# SensorsOnly_v7.net
KiCad netlist of a schematic drawn in EAGLE
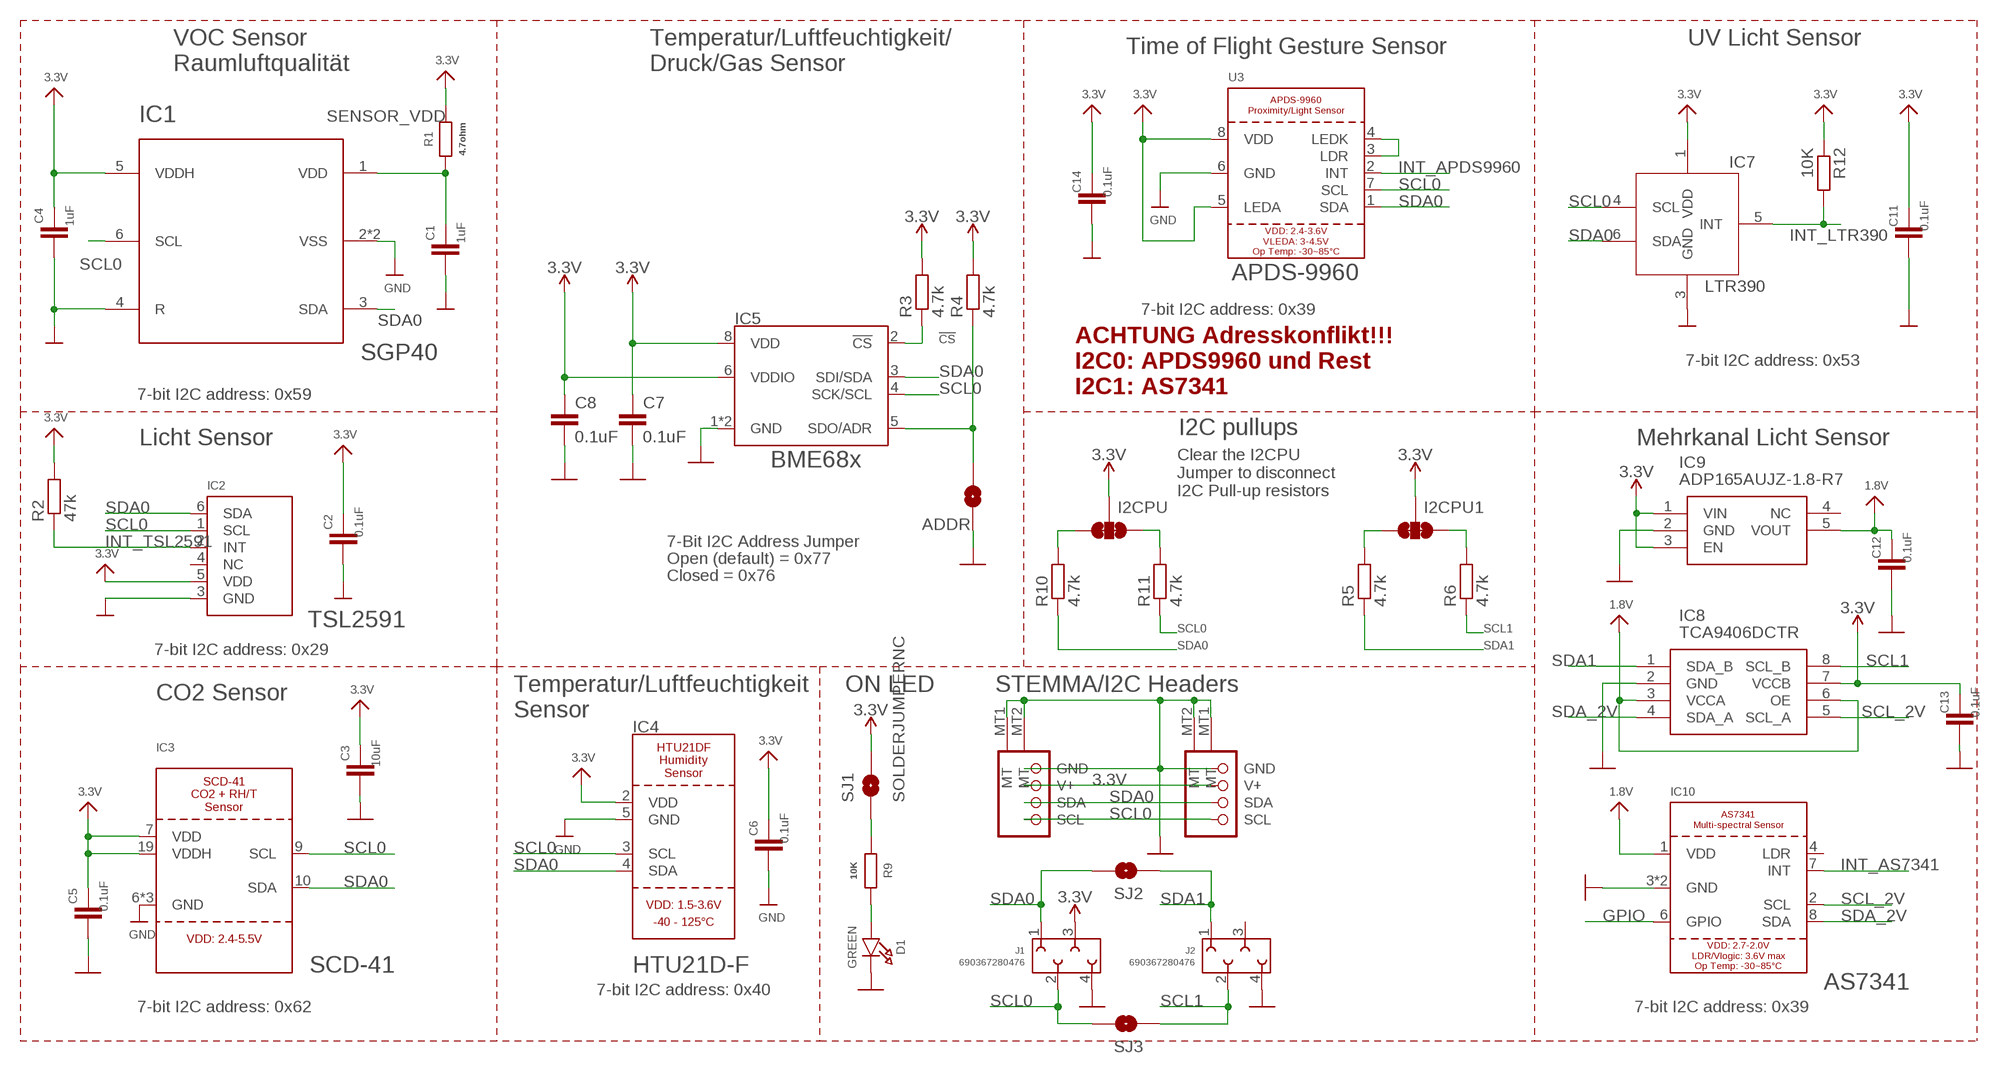
[diagram p0: schematic, sheet 1]

(export (version "E")
  (design (tool "Eeschema 10.0.6"))
  (components
    (comp (ref "ADDR")
      (value "JUMPER-SMT_2_NO_SILK")
      (footprint "eagle-import:SMT-JUMPER_2_NO_SILK")
      (libsource (lib "eagle-import") (part "JUMPER-SMT_2_NO_SILK"))
    )
    (comp (ref "C1")
      (value "1uF")
      (footprint "eagle-import:C0805")
      (libsource (lib "eagle-import") (part "C-EUC0805"))
    )
    (comp (ref "C2")
      (value "0.1uF")
      (footprint "eagle-import:C0603")
      (libsource (lib "eagle-import") (part "C-EUC0603"))
    )
    (comp (ref "C3")
      (value "10uF")
      (footprint "eagle-import:C0805")
      (libsource (lib "eagle-import") (part "C-EUC0805"))
    )
    (comp (ref "C4")
      (value "1uF")
      (footprint "eagle-import:C0805")
      (libsource (lib "eagle-import") (part "C-EUC0805"))
    )
    (comp (ref "C5")
      (value "0.1uF")
      (footprint "eagle-import:C0603")
      (libsource (lib "eagle-import") (part "C-EUC0603"))
    )
    (comp (ref "C6")
      (value "0.1uF")
      (footprint "eagle-import:C0603")
      (libsource (lib "eagle-import") (part "C-EUC0603"))
    )
    (comp (ref "C7")
      (value "0.1uF")
      (footprint "eagle-import:C0603")
      (libsource (lib "eagle-import") (part "C-EUC0603"))
    )
    (comp (ref "C8")
      (value "0.1uF")
      (footprint "eagle-import:C0603")
      (libsource (lib "eagle-import") (part "C-EUC0603"))
    )
    (comp (ref "C11")
      (value "0.1uF")
      (footprint "eagle-import:C0603")
      (libsource (lib "eagle-import") (part "C-EUC0603"))
    )
    (comp (ref "C12")
      (value "0.1uF")
      (footprint "eagle-import:C0603")
      (libsource (lib "eagle-import") (part "C-EUC0603"))
    )
    (comp (ref "C13")
      (value "0.1uF")
      (footprint "eagle-import:C0603")
      (libsource (lib "eagle-import") (part "C-EUC0603"))
    )
    (comp (ref "C14")
      (value "0.1uF")
      (footprint "eagle-import:C0603")
      (libsource (lib "eagle-import") (part "C-EUC0603"))
    )
    (comp (ref "D1")
      (value "GREEN")
      (footprint "eagle-import:CHIPLED_0603_NOOUTLINE")
      (libsource (lib "eagle-import") (part "LED0603_NOOUTLINE"))
    )
    (comp (ref "I2CPU")
      (value "I2C PU")
      (footprint "eagle-import:SMT-JUMPER_3_2-NC_TRACE_SILK")
      (libsource (lib "eagle-import") (part "JUMPER-SMT_3_2-NC_TRACE_SILK"))
    )
    (comp (ref "I2CPU1")
      (value "I2C PU")
      (footprint "eagle-import:SMT-JUMPER_3_2-NC_TRACE_SILK")
      (libsource (lib "eagle-import") (part "JUMPER-SMT_3_2-NC_TRACE_SILK"))
    )
    (comp (ref "IC1")
      (value "SGP40")
      (footprint "eagle-import:SGP30")
      (libsource (lib "eagle-import") (part "SGP30"))
    )
    (comp (ref "IC2")
      (value "TSL2591")
      (footprint "eagle-import:DFN6_TAOS")
      (libsource (lib "eagle-import") (part "LIGHT_TSL2591"))
    )
    (comp (ref "IC3")
      (value "SCD-41")
      (footprint "eagle-import:SCD41")
      (libsource (lib "eagle-import") (part "SCD-41"))
    )
    (comp (ref "IC4")
      (value "HTU21D-F")
      (footprint "eagle-import:HTU21DF")
      (libsource (lib "eagle-import") (part "HTU21DF"))
    )
    (comp (ref "IC5")
      (value "BME680 Air Quality Sensor")
      (footprint "eagle-import:LGA3.0X3.0")
      (libsource (lib "eagle-import") (part "BME680-LGA"))
    )
    (comp (ref "IC7")
      (value "LTR390")
      (footprint "eagle-import:LTR390")
      (libsource (lib "eagle-import") (part "LTR390"))
    )
    (comp (ref "IC8")
      (value "TCA9406DCTR")
      (footprint "eagle-import:SOP65P400X130-8N")
      (fields (field (name "MOUSER_PART_NUMBER") "595-TCA9406DCTR"))
      (libsource (lib "eagle-import") (part "TCA9406DCTR"))
    )
    (comp (ref "IC9")
      (value "ADP165AUJZ-1.8-R7")
      (footprint "eagle-import:SOT95P280X100-5N")
      (fields
        (field (name "MANUFACTURER_PART_NUMBER") "ADP165AUJZ-3.3-R7")
        (field (name "MOUSER_PART_NUMBER") "584-ADP165AUJZ3.3R7")
      )
      (libsource (lib "eagle-import") (part "ADP165AUJZ-3.3-R7"))
    )
    (comp (ref "IC10")
      (value "AS7341")
      (footprint "eagle-import:AS7341")
      (libsource (lib "eagle-import") (part "AS7341"))
    )
    (comp (ref "J1")
      (value "690367280476")
      (footprint "eagle-import:690367280476")
      (libsource (lib "eagle-import") (part "690367280476"))
    )
    (comp (ref "J2")
      (value "690367280476")
      (footprint "eagle-import:690367280476")
      (libsource (lib "eagle-import") (part "690367280476"))
    )
    (comp (ref "QWIIC1")
      (value "STEMMA_I2C_QT")
      (footprint "eagle-import:JST_SH4")
      (libsource (lib "eagle-import") (part "STEMMA_I2C_QT"))
    )
    (comp (ref "QWIIC2")
      (value "STEMMA_I2C_QT")
      (footprint "eagle-import:JST_SH4")
      (libsource (lib "eagle-import") (part "STEMMA_I2C_QT"))
    )
    (comp (ref "R1")
      (value "4.7ohm")
      (footprint "eagle-import:R0603")
      (libsource (lib "eagle-import") (part "R-EU_R0603"))
    )
    (comp (ref "R2")
      (value "47k")
      (footprint "eagle-import:R0603")
      (libsource (lib "eagle-import") (part "R-EU_R0603"))
    )
    (comp (ref "R3")
      (value "4.7k")
      (footprint "eagle-import:R0603")
      (libsource (lib "eagle-import") (part "R-EU_R0603"))
    )
    (comp (ref "R4")
      (value "4.7k")
      (footprint "eagle-import:R0603")
      (libsource (lib "eagle-import") (part "R-EU_R0603"))
    )
    (comp (ref "R5")
      (value "4.7k")
      (footprint "eagle-import:R0603")
      (libsource (lib "eagle-import") (part "R-EU_R0603"))
    )
    (comp (ref "R6")
      (value "4.7k")
      (footprint "eagle-import:R0603")
      (libsource (lib "eagle-import") (part "R-EU_R0603"))
    )
    (comp (ref "R9")
      (value "10K")
      (footprint "eagle-import:R0603")
      (libsource (lib "eagle-import") (part "R-EU_R0603"))
    )
    (comp (ref "R10")
      (value "4.7k")
      (footprint "eagle-import:R0603")
      (libsource (lib "eagle-import") (part "R-EU_R0603"))
    )
    (comp (ref "R11")
      (value "4.7k")
      (footprint "eagle-import:R0603")
      (libsource (lib "eagle-import") (part "R-EU_R0603"))
    )
    (comp (ref "R12")
      (value "10K")
      (footprint "eagle-import:R0603")
      (libsource (lib "eagle-import") (part "R-EU_R0603"))
    )
    (comp (ref "SJ1")
      (value "SOLDERJUMPERNC")
      (footprint "eagle-import:SJ_2S")
      (libsource (lib "eagle-import") (part "SOLDERJUMPERNC"))
    )
    (comp (ref "SJ2")
      (value "SOLDERJUMPERNC")
      (footprint "eagle-import:SJ_2S")
      (libsource (lib "eagle-import") (part "SOLDERJUMPERNC"))
    )
    (comp (ref "SJ3")
      (value "SOLDERJUMPERNC")
      (footprint "eagle-import:SJ_2S")
      (libsource (lib "eagle-import") (part "SOLDERJUMPERNC"))
    )
    (comp (ref "U3")
      (value "APDS-9960")
      (footprint "eagle-import:APDS-9960")
      (libsource (lib "eagle-import") (part "APDS-9960"))
    )
  )
  (nets
    (net (code "1") (name "/GPIO") (class "Default")
      (node (ref "IC10") (pin "6") (pinfunction "GPIO_6") (pintype "power_in"))
    )
    (net (code "2") (name "/INT_APDS9960") (class "Default")
      (node (ref "U3") (pin "2") (pinfunction "INT_2") (pintype "output"))
    )
    (net (code "3") (name "/INT_AS7341") (class "Default")
      (node (ref "IC10") (pin "7") (pinfunction "INT_7") (pintype "output"))
    )
    (net (code "4") (name "/INT_LTR390") (class "Default")
      (node (ref "IC7") (pin "5") (pinfunction "INT_5") (pintype "bidirectional"))
      (node (ref "R12") (pin "2") (pinfunction "2_2") (pintype "passive"))
    )
    (net (code "5") (name "/INT_TSL2591") (class "Default")
      (node (ref "IC2") (pin "2") (pinfunction "INT_2") (pintype "output"))
      (node (ref "R2") (pin "1") (pinfunction "1_1") (pintype "passive"))
    )
    (net (code "6") (name "/SCL_2V") (class "Default")
      (node (ref "IC10") (pin "2") (pinfunction "SCL_2") (pintype "input"))
      (node (ref "IC8") (pin "5") (pinfunction "SCL_A_5") (pintype "bidirectional"))
    )
    (net (code "7") (name "/SDA_2V") (class "Default")
      (node (ref "IC10") (pin "8") (pinfunction "SDA_8") (pintype "bidirectional"))
      (node (ref "IC8") (pin "4") (pinfunction "SDA_A_4") (pintype "bidirectional"))
    )
    (net (code "8") (name "/SENSOR_VDD") (class "Default")
      (node (ref "C1") (pin "1") (pinfunction "1_1") (pintype "passive"))
      (node (ref "IC1") (pin "1") (pinfunction "VDD_1") (pintype "bidirectional"))
      (node (ref "R1") (pin "1") (pinfunction "1_1") (pintype "passive"))
    )
    (net (code "9") (name "/~{CS}") (class "Default")
      (node (ref "IC5") (pin "2") (pinfunction "~{CS}_2") (pintype "bidirectional"))
      (node (ref "R3") (pin "1") (pinfunction "1_1") (pintype "passive"))
    )
    (net (code "10") (name "1.8V") (class "Default")
      (node (ref "C12") (pin "1") (pinfunction "1_1") (pintype "passive"))
      (node (ref "IC10") (pin "1") (pinfunction "VDD_1") (pintype "power_in"))
      (node (ref "IC8") (pin "3") (pinfunction "VCCA_3") (pintype "bidirectional"))
      (node (ref "IC8") (pin "6") (pinfunction "OE_6") (pintype "bidirectional"))
      (node (ref "IC9") (pin "5") (pinfunction "VOUT_5") (pintype "bidirectional"))
    )
    (net (code "11") (name "3.3V") (class "Default")
      (node (ref "C11") (pin "1") (pinfunction "1_1") (pintype "passive"))
      (node (ref "C13") (pin "1") (pinfunction "1_1") (pintype "passive"))
      (node (ref "C14") (pin "1") (pinfunction "1_1") (pintype "passive"))
      (node (ref "C2") (pin "1") (pinfunction "1_1") (pintype "passive"))
      (node (ref "C3") (pin "1") (pinfunction "1_1") (pintype "passive"))
      (node (ref "C4") (pin "1") (pinfunction "1_1") (pintype "passive"))
      (node (ref "C5") (pin "1") (pinfunction "1_1") (pintype "passive"))
      (node (ref "C6") (pin "1") (pinfunction "1_1") (pintype "passive"))
      (node (ref "C7") (pin "1") (pinfunction "1_1") (pintype "passive"))
      (node (ref "C8") (pin "1") (pinfunction "1_1") (pintype "passive"))
      (node (ref "I2CPU") (pin "2") (pinfunction "2_2") (pintype "passive"))
      (node (ref "I2CPU1") (pin "2") (pinfunction "2_2") (pintype "passive"))
      (node (ref "IC1") (pin "5") (pinfunction "VDDH_5") (pintype "bidirectional"))
      (node (ref "IC2") (pin "5") (pinfunction "VDD_5") (pintype "power_in"))
      (node (ref "IC3") (pin "19") (pinfunction "VDDH_19") (pintype "power_in"))
      (node (ref "IC3") (pin "7") (pinfunction "VDD_7") (pintype "power_in"))
      (node (ref "IC4") (pin "2") (pinfunction "VDD_2") (pintype "power_in"))
      (node (ref "IC5") (pin "6") (pinfunction "VDDIO_6") (pintype "bidirectional"))
      (node (ref "IC5") (pin "8") (pinfunction "VDD_8") (pintype "bidirectional"))
      (node (ref "IC7") (pin "1") (pinfunction "VDD_1") (pintype "power_in"))
      (node (ref "IC8") (pin "7") (pinfunction "VCCB_7") (pintype "bidirectional"))
      (node (ref "IC9") (pin "1") (pinfunction "VIN_1") (pintype "bidirectional"))
      (node (ref "IC9") (pin "3") (pinfunction "EN_3") (pintype "bidirectional"))
      (node (ref "J1") (pin "3") (pinfunction "3_3") (pintype "passive"))
      (node (ref "QWIIC1") (pin "2") (pinfunction "V+_2") (pintype "passive"))
      (node (ref "QWIIC2") (pin "2") (pinfunction "V+_2") (pintype "passive"))
      (node (ref "R1") (pin "2") (pinfunction "2_2") (pintype "passive"))
      (node (ref "R12") (pin "1") (pinfunction "1_1") (pintype "passive"))
      (node (ref "R2") (pin "2") (pinfunction "2_2") (pintype "passive"))
      (node (ref "R3") (pin "2") (pinfunction "2_2") (pintype "passive"))
      (node (ref "R4") (pin "2") (pinfunction "2_2") (pintype "passive"))
      (node (ref "SJ1") (pin "2") (pinfunction "2_2") (pintype "passive"))
      (node (ref "U3") (pin "5") (pinfunction "LEDA_5") (pintype "power_in"))
      (node (ref "U3") (pin "8") (pinfunction "VDD_8") (pintype "power_in"))
    )
    (net (code "12") (name "GND") (class "Default")
      (node (ref "ADDR") (pin "1") (pinfunction "1_1") (pintype "passive"))
      (node (ref "C1") (pin "2") (pinfunction "2_2") (pintype "passive"))
      (node (ref "C11") (pin "2") (pinfunction "2_2") (pintype "passive"))
      (node (ref "C12") (pin "2") (pinfunction "2_2") (pintype "passive"))
      (node (ref "C13") (pin "2") (pinfunction "2_2") (pintype "passive"))
      (node (ref "C14") (pin "2") (pinfunction "2_2") (pintype "passive"))
      (node (ref "C2") (pin "2") (pinfunction "2_2") (pintype "passive"))
      (node (ref "C3") (pin "2") (pinfunction "2_2") (pintype "passive"))
      (node (ref "C4") (pin "2") (pinfunction "2_2") (pintype "passive"))
      (node (ref "C5") (pin "2") (pinfunction "2_2") (pintype "passive"))
      (node (ref "C6") (pin "2") (pinfunction "2_2") (pintype "passive"))
      (node (ref "C7") (pin "2") (pinfunction "2_2") (pintype "passive"))
      (node (ref "C8") (pin "2") (pinfunction "2_2") (pintype "passive"))
      (node (ref "D1") (pin "C") (pinfunction "C_C") (pintype "passive"))
      (node (ref "IC1") (pin "2") (pinfunction "VSS_2") (pintype "bidirectional"))
      (node (ref "IC1") (pin "4") (pinfunction "R_4") (pintype "bidirectional"))
      (node (ref "IC1") (pin "P$7") (pinfunction "VSS_P$7") (pintype "bidirectional"))
      (node (ref "IC10") (pin "3") (pinfunction "GND_3") (pintype "power_in"))
      (node (ref "IC10") (pin "5") (pinfunction "GND_5") (pintype "power_in"))
      (node (ref "IC2") (pin "3") (pinfunction "GND_3") (pintype "power_in"))
      (node (ref "IC3") (pin "20") (pinfunction "GND_20") (pintype "power_in"))
      (node (ref "IC3") (pin "6") (pinfunction "GND_6") (pintype "power_in"))
      (node (ref "IC3") (pin "P$1") (pinfunction "GND_P$1") (pintype "power_in"))
      (node (ref "IC4") (pin "5") (pinfunction "GND_5") (pintype "power_in"))
      (node (ref "IC5") (pin "1") (pinfunction "GND_1") (pintype "bidirectional"))
      (node (ref "IC5") (pin "7") (pinfunction "GND_7") (pintype "bidirectional"))
      (node (ref "IC7") (pin "3") (pinfunction "GND_3") (pintype "power_in"))
      (node (ref "IC8") (pin "2") (pinfunction "GND_2") (pintype "bidirectional"))
      (node (ref "IC9") (pin "2") (pinfunction "GND_2") (pintype "bidirectional"))
      (node (ref "J1") (pin "4") (pinfunction "4_4") (pintype "passive"))
      (node (ref "J2") (pin "4") (pinfunction "4_4") (pintype "passive"))
      (node (ref "QWIIC1") (pin "1") (pinfunction "GND_1") (pintype "passive"))
      (node (ref "QWIIC1") (pin "MT1") (pinfunction "MT_MT1") (pintype "bidirectional"))
      (node (ref "QWIIC1") (pin "MT2") (pinfunction "MT_MT2") (pintype "bidirectional"))
      (node (ref "QWIIC2") (pin "1") (pinfunction "GND_1") (pintype "passive"))
      (node (ref "QWIIC2") (pin "MT1") (pinfunction "MT_MT1") (pintype "bidirectional"))
      (node (ref "QWIIC2") (pin "MT2") (pinfunction "MT_MT2") (pintype "bidirectional"))
      (node (ref "U3") (pin "6") (pinfunction "GND_6") (pintype "power_in"))
    )
    (net (code "13") (name "Net-(D1-PadA)") (class "Default")
      (node (ref "D1") (pin "A") (pinfunction "A_A") (pintype "passive"))
      (node (ref "R9") (pin "2") (pinfunction "2_2") (pintype "passive"))
    )
    (net (code "14") (name "Net-(I2CPU-Pad1)") (class "Default")
      (node (ref "I2CPU") (pin "1") (pinfunction "1_1") (pintype "passive"))
      (node (ref "R11") (pin "2") (pinfunction "2_2") (pintype "passive"))
    )
    (net (code "15") (name "Net-(I2CPU-Pad3)") (class "Default")
      (node (ref "I2CPU") (pin "3") (pinfunction "3_3") (pintype "passive"))
      (node (ref "R10") (pin "2") (pinfunction "2_2") (pintype "passive"))
    )
    (net (code "16") (name "Net-(I2CPU1-Pad1)") (class "Default")
      (node (ref "I2CPU1") (pin "1") (pinfunction "1_1") (pintype "passive"))
      (node (ref "R6") (pin "2") (pinfunction "2_2") (pintype "passive"))
    )
    (net (code "17") (name "Net-(I2CPU1-Pad3)") (class "Default")
      (node (ref "I2CPU1") (pin "3") (pinfunction "3_3") (pintype "passive"))
      (node (ref "R5") (pin "2") (pinfunction "2_2") (pintype "passive"))
    )
    (net (code "18") (name "Net-(IC5-SDO{slash}ADR)") (class "Default")
      (node (ref "ADDR") (pin "2") (pinfunction "2_2") (pintype "passive"))
      (node (ref "IC5") (pin "5") (pinfunction "SDO/ADR_5") (pintype "bidirectional"))
      (node (ref "R4") (pin "1") (pinfunction "1_1") (pintype "passive"))
    )
    (net (code "19") (name "Net-(R9-Pad1)") (class "Default")
      (node (ref "R9") (pin "1") (pinfunction "1_1") (pintype "passive"))
      (node (ref "SJ1") (pin "1") (pinfunction "1_1") (pintype "passive"))
    )
    (net (code "20") (name "Net-(U3-LDR)") (class "Default")
      (node (ref "U3") (pin "3") (pinfunction "LDR_3") (pintype "bidirectional"))
      (node (ref "U3") (pin "4") (pinfunction "LEDK_4") (pintype "bidirectional"))
    )
    (net (code "21") (name "SCL0") (class "Default")
      (node (ref "IC1") (pin "6") (pinfunction "SCL_6") (pintype "bidirectional"))
      (node (ref "IC2") (pin "1") (pinfunction "SCL_1") (pintype "bidirectional"))
      (node (ref "IC3") (pin "9") (pinfunction "SCL_9") (pintype "input"))
      (node (ref "IC4") (pin "3") (pinfunction "SCL_3") (pintype "input"))
      (node (ref "IC5") (pin "4") (pinfunction "SCK/SCL_4") (pintype "bidirectional"))
      (node (ref "IC7") (pin "4") (pinfunction "SCL_4") (pintype "bidirectional"))
      (node (ref "J1") (pin "2") (pinfunction "2_2") (pintype "passive"))
      (node (ref "QWIIC1") (pin "4") (pinfunction "SCL_4") (pintype "passive"))
      (node (ref "QWIIC2") (pin "4") (pinfunction "SCL_4") (pintype "passive"))
      (node (ref "R11") (pin "1") (pinfunction "1_1") (pintype "passive"))
      (node (ref "SJ3") (pin "2") (pinfunction "2_2") (pintype "passive"))
      (node (ref "U3") (pin "7") (pinfunction "SCL_7") (pintype "input"))
    )
    (net (code "22") (name "SCL1") (class "Default")
      (node (ref "IC8") (pin "8") (pinfunction "SCL_B_8") (pintype "bidirectional"))
      (node (ref "J2") (pin "2") (pinfunction "2_2") (pintype "passive"))
      (node (ref "R6") (pin "1") (pinfunction "1_1") (pintype "passive"))
      (node (ref "SJ3") (pin "1") (pinfunction "1_1") (pintype "passive"))
    )
    (net (code "23") (name "SDA0") (class "Default")
      (node (ref "IC1") (pin "3") (pinfunction "SDA_3") (pintype "bidirectional"))
      (node (ref "IC2") (pin "6") (pinfunction "SDA_6") (pintype "bidirectional"))
      (node (ref "IC3") (pin "10") (pinfunction "SDA_10") (pintype "bidirectional"))
      (node (ref "IC4") (pin "4") (pinfunction "SDA_4") (pintype "bidirectional"))
      (node (ref "IC5") (pin "3") (pinfunction "SDI/SDA_3") (pintype "bidirectional"))
      (node (ref "IC7") (pin "6") (pinfunction "SDA_6") (pintype "bidirectional"))
      (node (ref "J1") (pin "1") (pinfunction "1_1") (pintype "passive"))
      (node (ref "QWIIC1") (pin "3") (pinfunction "SDA_3") (pintype "passive"))
      (node (ref "QWIIC2") (pin "3") (pinfunction "SDA_3") (pintype "passive"))
      (node (ref "R10") (pin "1") (pinfunction "1_1") (pintype "passive"))
      (node (ref "SJ2") (pin "2") (pinfunction "2_2") (pintype "passive"))
      (node (ref "U3") (pin "1") (pinfunction "SDA_1") (pintype "bidirectional"))
    )
    (net (code "24") (name "SDA1") (class "Default")
      (node (ref "IC8") (pin "1") (pinfunction "SDA_B_1") (pintype "bidirectional"))
      (node (ref "J2") (pin "1") (pinfunction "1_1") (pintype "passive"))
      (node (ref "R5") (pin "1") (pinfunction "1_1") (pintype "passive"))
      (node (ref "SJ2") (pin "1") (pinfunction "1_1") (pintype "passive"))
    )
    (net (code "25") (name "unconnected-(IC2-NC-Pad4)") (class "Default")
      (node (ref "IC2") (pin "4") (pinfunction "NC_4") (pintype "no_connect"))
    )
    (net (code "26") (name "unconnected-(IC9-NC-Pad4)") (class "Default")
      (node (ref "IC9") (pin "4") (pinfunction "NC_4") (pintype "no_connect"))
    )
    (net (code "27") (name "unconnected-(IC10-LDR-Pad4)") (class "Default")
      (node (ref "IC10") (pin "4") (pinfunction "LDR_4") (pintype "bidirectional"))
    )
    (net (code "28") (name "unconnected-(J2-Pad3)") (class "Default")
      (node (ref "J2") (pin "3") (pinfunction "3_3") (pintype "passive"))
    )
  )
)
